# GSM_GNSS_Module.net
KiCad netlist of a schematic drawn in Altium Designer
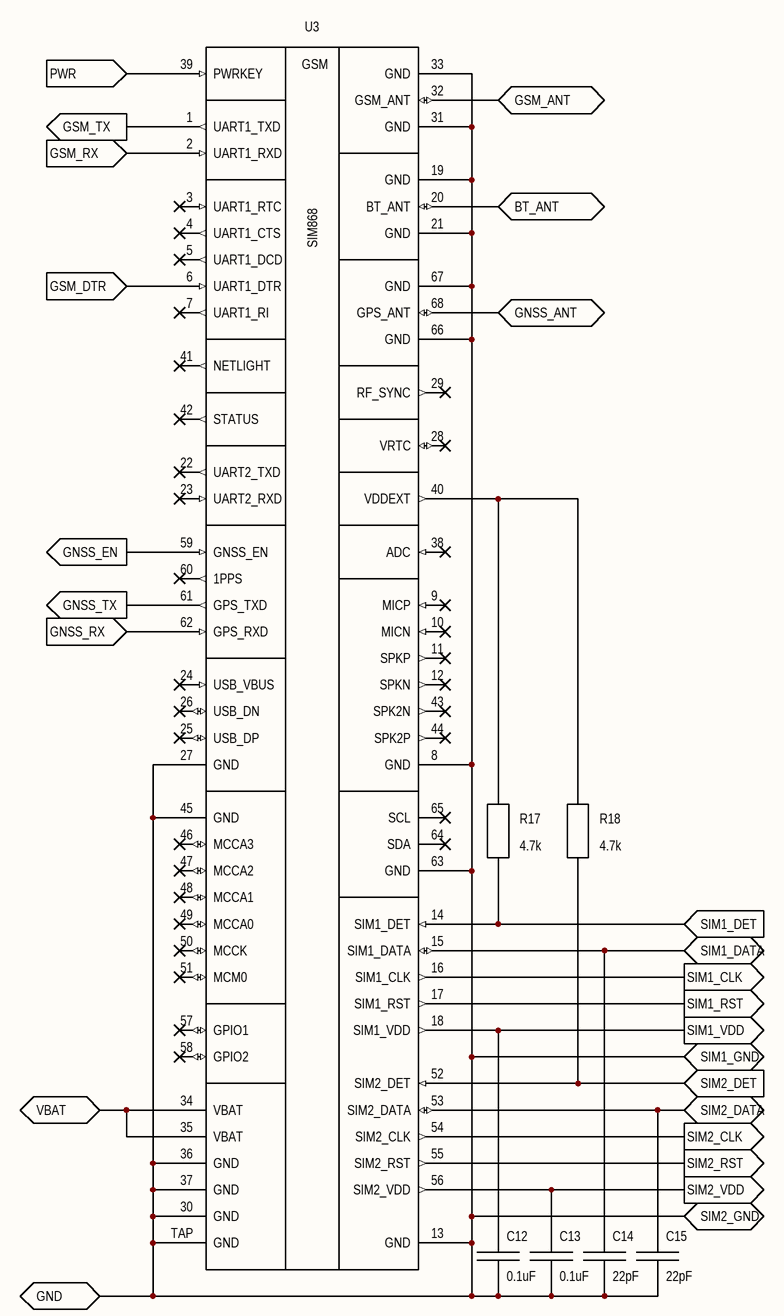
[diagram p0: GSM GNSS Module.SchDoc]

(export (version "E")
  (design (tool "Eeschema 10.0.6"))
  (components
    (comp (ref "C12")
      (value "0.1uF")
      (footprint "CAPC1608L")
      (description "Capacitor Ceramic 0.1uF 25V 0603(1608)")
      (fields (field (name "TOLERANCE") "±10%") (field (name "MANUFACTURER") "Yageo"))
      (libsource (lib "Capacitors") (part "CC0603KRX7R8BB104"))
    )
    (comp (ref "C13")
      (value "0.1uF")
      (footprint "CAPC1608L")
      (description "Capacitor Ceramic 0.1uF 25V 0603(1608)")
      (fields (field (name "TOLERANCE") "±10%") (field (name "MANUFACTURER") "Yageo"))
      (libsource (lib "Capacitors") (part "CC0603KRX7R8BB104"))
    )
    (comp (ref "C14")
      (value "22pF")
      (footprint "CAPC1608L")
      (description "Capacitor Ceramic 22pF 50V 0603(1608)")
      (fields (field (name "TOLERANCE") "±5%") (field (name "MANUFACTURER") "Yageo"))
      (libsource (lib "Capacitors") (part "CC0201JRNPO9BN220"))
    )
    (comp (ref "C15")
      (value "22pF")
      (footprint "CAPC1608L")
      (description "Capacitor Ceramic 22pF 50V 0603(1608)")
      (fields (field (name "TOLERANCE") "±5%") (field (name "MANUFACTURER") "Yageo"))
      (libsource (lib "Capacitors") (part "CC0201JRNPO9BN220"))
    )
    (comp (ref "R17")
      (value "4.7k")
      (footprint "RESC1608L")
      (description "Resistor Ceramic 4.7k 0.1W 0603(1608)")
      (fields (field (name "MANUFACTURER") "Yageo") (field (name "TOLERANCE") "±5%"))
      (libsource (lib "Resistors") (part "RC0603JR-074K7L"))
    )
    (comp (ref "R18")
      (value "4.7k")
      (footprint "RESC1608L")
      (description "Resistor Ceramic 4.7k 0.1W 0603(1608)")
      (fields (field (name "MANUFACTURER") "Yageo") (field (name "TOLERANCE") "±5%"))
      (libsource (lib "Resistors") (part "RC0603JR-074K7L"))
    )
    (comp (ref "U3")
      (value "SIM868")
      (footprint "SIM868")
      (description "GSM/GPRS/GNSS module")
      (fields (field (name "MANUFACTURER") "SIMCOM"))
      (libsource (lib "Wireless") (part "SIM868"))
    )
  )
  (nets
    (net (code "1") (name "/BT_ANT") (class "Default")
      (node (ref "U3") (pin "20") (pinfunction "BT_ANT_20") (pintype "bidirectional"))
    )
    (net (code "2") (name "/GND") (class "Default")
      (node (ref "C12") (pin "2") (pinfunction "2_2") (pintype "passive"))
      (node (ref "C13") (pin "2") (pinfunction "2_2") (pintype "passive"))
      (node (ref "C14") (pin "2") (pinfunction "2_2") (pintype "passive"))
      (node (ref "C15") (pin "2") (pinfunction "2_2") (pintype "passive"))
      (node (ref "U3") (pin "13") (pinfunction "GND_13") (pintype "passive"))
      (node (ref "U3") (pin "19") (pinfunction "GND_19") (pintype "passive"))
      (node (ref "U3") (pin "21") (pinfunction "GND_21") (pintype "passive"))
      (node (ref "U3") (pin "27") (pinfunction "GND_27") (pintype "passive"))
      (node (ref "U3") (pin "30") (pinfunction "GND_30") (pintype "passive"))
      (node (ref "U3") (pin "31") (pinfunction "GND_31") (pintype "passive"))
      (node (ref "U3") (pin "33") (pinfunction "GND_33") (pintype "passive"))
      (node (ref "U3") (pin "36") (pinfunction "GND_36") (pintype "passive"))
      (node (ref "U3") (pin "37") (pinfunction "GND_37") (pintype "passive"))
      (node (ref "U3") (pin "45") (pinfunction "GND_45") (pintype "passive"))
      (node (ref "U3") (pin "63") (pinfunction "GND_63") (pintype "passive"))
      (node (ref "U3") (pin "66") (pinfunction "GND_66") (pintype "passive"))
      (node (ref "U3") (pin "67") (pinfunction "GND_67") (pintype "passive"))
      (node (ref "U3") (pin "8") (pinfunction "GND_8") (pintype "passive"))
      (node (ref "U3") (pin "TAP") (pinfunction "GND_TAP") (pintype "passive"))
    )
    (net (code "3") (name "/GNSS_ANT") (class "Default")
      (node (ref "U3") (pin "68") (pinfunction "GPS_ANT_68") (pintype "bidirectional"))
    )
    (net (code "4") (name "/GNSS_EN") (class "Default")
      (node (ref "U3") (pin "59") (pinfunction "GNSS_EN_59") (pintype "input"))
    )
    (net (code "5") (name "/GNSS_RX") (class "Default")
      (node (ref "U3") (pin "62") (pinfunction "GPS_RXD_62") (pintype "input"))
    )
    (net (code "6") (name "/GNSS_TX") (class "Default")
      (node (ref "U3") (pin "61") (pinfunction "GPS_TXD_61") (pintype "output"))
    )
    (net (code "7") (name "/GSM_ANT") (class "Default")
      (node (ref "U3") (pin "32") (pinfunction "GSM_ANT_32") (pintype "bidirectional"))
    )
    (net (code "8") (name "/GSM_DTR") (class "Default")
      (node (ref "U3") (pin "6") (pinfunction "UART1_DTR_6") (pintype "input"))
    )
    (net (code "9") (name "/GSM_RX") (class "Default")
      (node (ref "U3") (pin "2") (pinfunction "UART1_RXD_2") (pintype "input"))
    )
    (net (code "10") (name "/GSM_TX") (class "Default")
      (node (ref "U3") (pin "1") (pinfunction "UART1_TXD_1") (pintype "output"))
    )
    (net (code "11") (name "/PWR") (class "Default")
      (node (ref "U3") (pin "39") (pinfunction "PWRKEY_39") (pintype "input"))
    )
    (net (code "12") (name "/SIM1_CLK") (class "Default")
      (node (ref "U3") (pin "16") (pinfunction "SIM1_CLK_16") (pintype "output"))
    )
    (net (code "13") (name "/SIM1_DATA") (class "Default")
      (node (ref "C14") (pin "1") (pinfunction "1_1") (pintype "passive"))
      (node (ref "U3") (pin "15") (pinfunction "SIM1_DATA_15") (pintype "bidirectional"))
    )
    (net (code "14") (name "/SIM1_DET") (class "Default")
      (node (ref "R17") (pin "2") (pinfunction "2_2") (pintype "passive"))
      (node (ref "U3") (pin "14") (pinfunction "SIM1_DET_14") (pintype "input"))
    )
    (net (code "15") (name "/SIM1_RST") (class "Default")
      (node (ref "U3") (pin "17") (pinfunction "SIM1_RST_17") (pintype "output"))
    )
    (net (code "16") (name "/SIM1_VDD") (class "Default")
      (node (ref "C12") (pin "1") (pinfunction "1_1") (pintype "passive"))
      (node (ref "U3") (pin "18") (pinfunction "SIM1_VDD_18") (pintype "output"))
    )
    (net (code "17") (name "/SIM2_CLK") (class "Default")
      (node (ref "U3") (pin "54") (pinfunction "SIM2_CLK_54") (pintype "output"))
    )
    (net (code "18") (name "/SIM2_DATA") (class "Default")
      (node (ref "C15") (pin "1") (pinfunction "1_1") (pintype "passive"))
      (node (ref "U3") (pin "53") (pinfunction "SIM2_DATA_53") (pintype "bidirectional"))
    )
    (net (code "19") (name "/SIM2_DET") (class "Default")
      (node (ref "R18") (pin "2") (pinfunction "2_2") (pintype "passive"))
      (node (ref "U3") (pin "52") (pinfunction "SIM2_DET_52") (pintype "input"))
    )
    (net (code "20") (name "/SIM2_RST") (class "Default")
      (node (ref "U3") (pin "55") (pinfunction "SIM2_RST_55") (pintype "output"))
    )
    (net (code "21") (name "/SIM2_VDD") (class "Default")
      (node (ref "C13") (pin "1") (pinfunction "1_1") (pintype "passive"))
      (node (ref "U3") (pin "56") (pinfunction "SIM2_VDD_56") (pintype "output"))
    )
    (net (code "22") (name "/VBAT") (class "Default")
      (node (ref "U3") (pin "34") (pinfunction "VBAT_34") (pintype "power_in"))
      (node (ref "U3") (pin "35") (pinfunction "VBAT_35") (pintype "power_in"))
    )
    (net (code "23") (name "Net-(U3-VDDEXT)") (class "Default")
      (node (ref "R17") (pin "1") (pinfunction "1_1") (pintype "passive"))
      (node (ref "R18") (pin "1") (pinfunction "1_1") (pintype "passive"))
      (node (ref "U3") (pin "40") (pinfunction "VDDEXT_40") (pintype "output"))
    )
    (net (code "24") (name "unconnected-(U3-1PPS-Pad60)") (class "Default")
      (node (ref "U3") (pin "60") (pinfunction "1PPS_60") (pintype "output+no_connect"))
    )
    (net (code "25") (name "unconnected-(U3-ADC-Pad38)") (class "Default")
      (node (ref "U3") (pin "38") (pinfunction "ADC_38") (pintype "input+no_connect"))
    )
    (net (code "26") (name "unconnected-(U3-GPIO1-Pad57)") (class "Default")
      (node (ref "U3") (pin "57") (pinfunction "GPIO1_57") (pintype "bidirectional+no_connect"))
    )
    (net (code "27") (name "unconnected-(U3-GPIO2-Pad58)") (class "Default")
      (node (ref "U3") (pin "58") (pinfunction "GPIO2_58") (pintype "bidirectional+no_connect"))
    )
    (net (code "28") (name "unconnected-(U3-MCCA0-Pad49)") (class "Default")
      (node (ref "U3") (pin "49") (pinfunction "MCCA0_49") (pintype "bidirectional+no_connect"))
    )
    (net (code "29") (name "unconnected-(U3-MCCA1-Pad48)") (class "Default")
      (node (ref "U3") (pin "48") (pinfunction "MCCA1_48") (pintype "bidirectional+no_connect"))
    )
    (net (code "30") (name "unconnected-(U3-MCCA2-Pad47)") (class "Default")
      (node (ref "U3") (pin "47") (pinfunction "MCCA2_47") (pintype "bidirectional+no_connect"))
    )
    (net (code "31") (name "unconnected-(U3-MCCA3-Pad46)") (class "Default")
      (node (ref "U3") (pin "46") (pinfunction "MCCA3_46") (pintype "bidirectional+no_connect"))
    )
    (net (code "32") (name "unconnected-(U3-MCCK-Pad50)") (class "Default")
      (node (ref "U3") (pin "50") (pinfunction "MCCK_50") (pintype "bidirectional+no_connect"))
    )
    (net (code "33") (name "unconnected-(U3-MCM0-Pad51)") (class "Default")
      (node (ref "U3") (pin "51") (pinfunction "MCM0_51") (pintype "bidirectional+no_connect"))
    )
    (net (code "34") (name "unconnected-(U3-MICN-Pad10)") (class "Default")
      (node (ref "U3") (pin "10") (pinfunction "MICN_10") (pintype "input+no_connect"))
    )
    (net (code "35") (name "unconnected-(U3-MICP-Pad9)") (class "Default")
      (node (ref "U3") (pin "9") (pinfunction "MICP_9") (pintype "input+no_connect"))
    )
    (net (code "36") (name "unconnected-(U3-NETLIGHT-Pad41)") (class "Default")
      (node (ref "U3") (pin "41") (pinfunction "NETLIGHT_41") (pintype "output+no_connect"))
    )
    (net (code "37") (name "unconnected-(U3-RF_SYNC-Pad29)") (class "Default")
      (node (ref "U3") (pin "29") (pinfunction "RF_SYNC_29") (pintype "output+no_connect"))
    )
    (net (code "38") (name "unconnected-(U3-SCL-Pad65)") (class "Default")
      (node (ref "U3") (pin "65") (pinfunction "SCL_65") (pintype "passive+no_connect"))
    )
    (net (code "39") (name "unconnected-(U3-SDA-Pad64)") (class "Default")
      (node (ref "U3") (pin "64") (pinfunction "SDA_64") (pintype "passive+no_connect"))
    )
    (net (code "40") (name "unconnected-(U3-SPK2N-Pad43)") (class "Default")
      (node (ref "U3") (pin "43") (pinfunction "SPK2N_43") (pintype "output+no_connect"))
    )
    (net (code "41") (name "unconnected-(U3-SPK2P-Pad44)") (class "Default")
      (node (ref "U3") (pin "44") (pinfunction "SPK2P_44") (pintype "output+no_connect"))
    )
    (net (code "42") (name "unconnected-(U3-SPKN-Pad12)") (class "Default")
      (node (ref "U3") (pin "12") (pinfunction "SPKN_12") (pintype "output+no_connect"))
    )
    (net (code "43") (name "unconnected-(U3-SPKP-Pad11)") (class "Default")
      (node (ref "U3") (pin "11") (pinfunction "SPKP_11") (pintype "output+no_connect"))
    )
    (net (code "44") (name "unconnected-(U3-STATUS-Pad42)") (class "Default")
      (node (ref "U3") (pin "42") (pinfunction "STATUS_42") (pintype "output+no_connect"))
    )
    (net (code "45") (name "unconnected-(U3-UART1_CTS-Pad4)") (class "Default")
      (node (ref "U3") (pin "4") (pinfunction "UART1_CTS_4") (pintype "output+no_connect"))
    )
    (net (code "46") (name "unconnected-(U3-UART1_DCD-Pad5)") (class "Default")
      (node (ref "U3") (pin "5") (pinfunction "UART1_DCD_5") (pintype "output+no_connect"))
    )
    (net (code "47") (name "unconnected-(U3-UART1_RI-Pad7)") (class "Default")
      (node (ref "U3") (pin "7") (pinfunction "UART1_RI_7") (pintype "output+no_connect"))
    )
    (net (code "48") (name "unconnected-(U3-UART1_RTC-Pad3)") (class "Default")
      (node (ref "U3") (pin "3") (pinfunction "UART1_RTC_3") (pintype "input+no_connect"))
    )
    (net (code "49") (name "unconnected-(U3-UART2_RXD-Pad23)") (class "Default")
      (node (ref "U3") (pin "23") (pinfunction "UART2_RXD_23") (pintype "input+no_connect"))
    )
    (net (code "50") (name "unconnected-(U3-UART2_TXD-Pad22)") (class "Default")
      (node (ref "U3") (pin "22") (pinfunction "UART2_TXD_22") (pintype "output+no_connect"))
    )
    (net (code "51") (name "unconnected-(U3-USB_DN-Pad26)") (class "Default")
      (node (ref "U3") (pin "26") (pinfunction "USB_DN_26") (pintype "bidirectional+no_connect"))
    )
    (net (code "52") (name "unconnected-(U3-USB_DP-Pad25)") (class "Default")
      (node (ref "U3") (pin "25") (pinfunction "USB_DP_25") (pintype "bidirectional+no_connect"))
    )
    (net (code "53") (name "unconnected-(U3-USB_VBUS-Pad24)") (class "Default")
      (node (ref "U3") (pin "24") (pinfunction "USB_VBUS_24") (pintype "input+no_connect"))
    )
    (net (code "54") (name "unconnected-(U3-VRTC-Pad28)") (class "Default")
      (node (ref "U3") (pin "28") (pinfunction "VRTC_28") (pintype "bidirectional+no_connect"))
    )
  )
)
